# juggling_ballsch.net
KiCad netlist of a schematic drawn in EAGLE
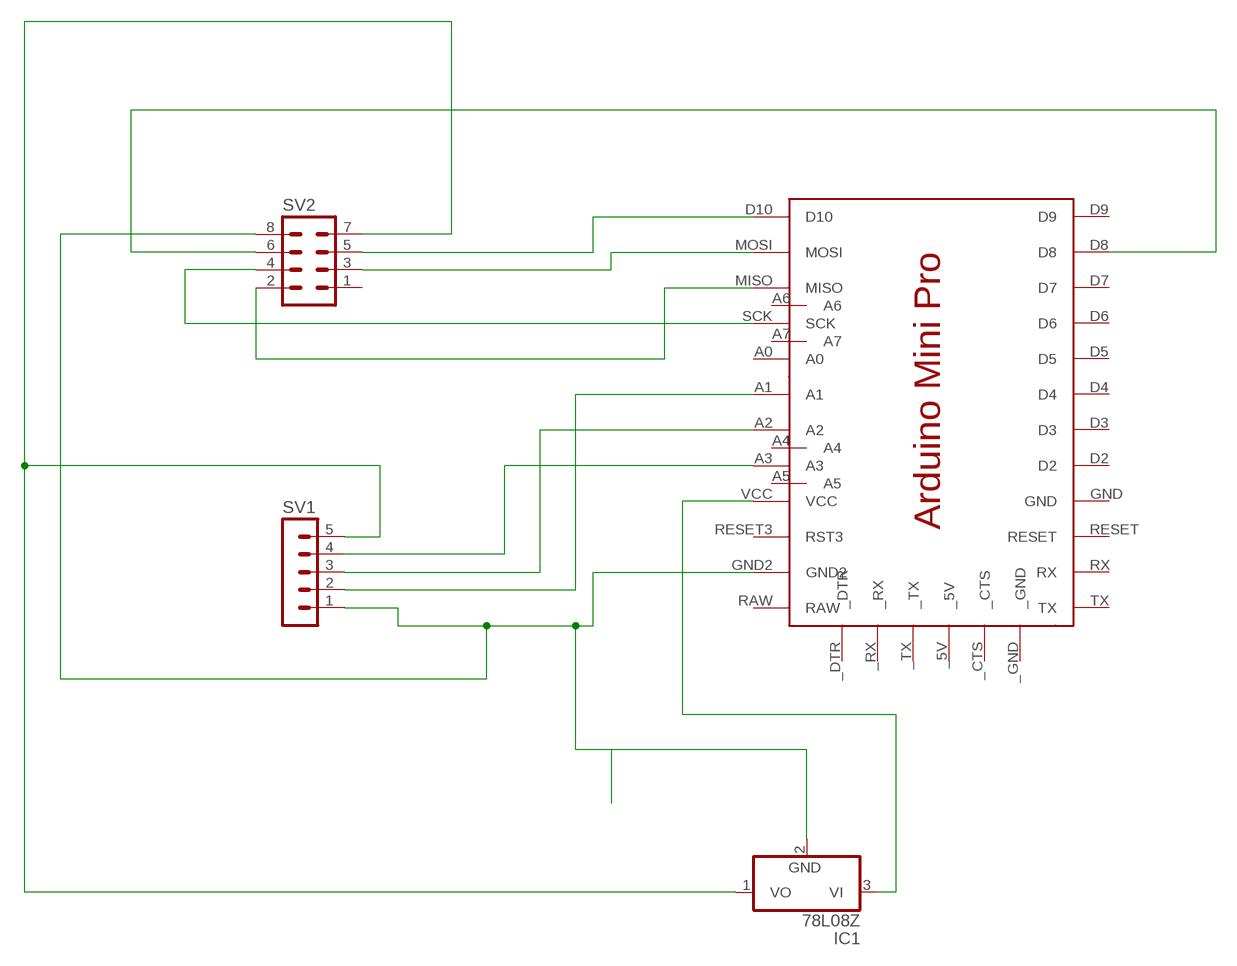
[diagram p0: schematic, sheet 1]

(export (version "E")
  (design (tool "Eeschema 10.0.6"))
  (components
    (comp (ref "IC1")
      (value "78L08Z")
      (footprint "eagle-import:TO92")
      (libsource (lib "eagle-import") (part "78ZL08"))
    )
    (comp (ref "SV1")
      (value "MA05-1")
      (footprint "eagle-import:MA05-1")
      (libsource (lib "eagle-import") (part "MA05-1"))
    )
    (comp (ref "SV2")
      (value "MA04-2")
      (footprint "eagle-import:MA04-2")
      (libsource (lib "eagle-import") (part "MA04-2"))
    )
    (comp (ref "U$1")
      (value "ARDMINIPRO")
      (footprint "eagle-import:ARDMINIPRO")
      (libsource (lib "eagle-import") (part "ARDMINIPRO"))
    )
  )
  (nets
    (net (code "1") (name "Net-(IC1-GND)") (class "Default")
      (node (ref "IC1") (pin "2") (pinfunction "GND_2") (pintype "passive"))
      (node (ref "SV1") (pin "1") (pinfunction "1_1") (pintype "passive"))
      (node (ref "SV2") (pin "8") (pinfunction "8_8") (pintype "passive"))
      (node (ref "U$1") (pin "GND2") (pinfunction "GND2_GND2") (pintype "bidirectional"))
    )
    (net (code "2") (name "Net-(IC1-VI)") (class "Default")
      (node (ref "IC1") (pin "3") (pinfunction "VI_3") (pintype "input"))
      (node (ref "U$1") (pin "VCC") (pinfunction "VCC_VCC") (pintype "bidirectional"))
    )
    (net (code "3") (name "Net-(IC1-VO)") (class "Default")
      (node (ref "IC1") (pin "1") (pinfunction "VO_1") (pintype "passive"))
      (node (ref "SV1") (pin "5") (pinfunction "5_5") (pintype "passive"))
      (node (ref "SV2") (pin "7") (pinfunction "7_7") (pintype "passive"))
    )
    (net (code "4") (name "Net-(SV1-Pad2)") (class "Default")
      (node (ref "SV1") (pin "2") (pinfunction "2_2") (pintype "passive"))
      (node (ref "U$1") (pin "A1") (pinfunction "A1_A1") (pintype "bidirectional"))
    )
    (net (code "5") (name "Net-(SV1-Pad3)") (class "Default")
      (node (ref "SV1") (pin "3") (pinfunction "3_3") (pintype "passive"))
      (node (ref "U$1") (pin "A2") (pinfunction "A2_A2") (pintype "bidirectional"))
    )
    (net (code "6") (name "Net-(SV1-Pad4)") (class "Default")
      (node (ref "SV1") (pin "4") (pinfunction "4_4") (pintype "passive"))
      (node (ref "U$1") (pin "A3") (pinfunction "A3_A3") (pintype "bidirectional"))
    )
    (net (code "7") (name "Net-(SV2-Pad2)") (class "Default")
      (node (ref "SV2") (pin "2") (pinfunction "2_2") (pintype "passive"))
      (node (ref "U$1") (pin "MISO") (pinfunction "MISO_MISO") (pintype "bidirectional"))
    )
    (net (code "8") (name "Net-(SV2-Pad3)") (class "Default")
      (node (ref "SV2") (pin "3") (pinfunction "3_3") (pintype "passive"))
      (node (ref "U$1") (pin "MOSI") (pinfunction "MOSI_MOSI") (pintype "bidirectional"))
    )
    (net (code "9") (name "Net-(SV2-Pad4)") (class "Default")
      (node (ref "SV2") (pin "4") (pinfunction "4_4") (pintype "passive"))
      (node (ref "U$1") (pin "SCK") (pinfunction "SCK_SCK") (pintype "bidirectional"))
    )
    (net (code "10") (name "Net-(SV2-Pad5)") (class "Default")
      (node (ref "SV2") (pin "5") (pinfunction "5_5") (pintype "passive"))
      (node (ref "U$1") (pin "D10") (pinfunction "D10_D10") (pintype "bidirectional"))
    )
    (net (code "11") (name "Net-(SV2-Pad6)") (class "Default")
      (node (ref "SV2") (pin "6") (pinfunction "6_6") (pintype "passive"))
      (node (ref "U$1") (pin "D8") (pinfunction "D8_D8") (pintype "bidirectional"))
    )
    (net (code "12") (name "unconnected-(SV2-Pad1)") (class "Default")
      (node (ref "SV2") (pin "1") (pinfunction "1_1") (pintype "passive"))
    )
    (net (code "13") (name "unconnected-(U$1-PadA0)") (class "Default")
      (node (ref "U$1") (pin "A0") (pinfunction "A0_A0") (pintype "bidirectional"))
    )
    (net (code "14") (name "unconnected-(U$1-PadA4)") (class "Default")
      (node (ref "U$1") (pin "A4") (pinfunction "A4_A4") (pintype "bidirectional"))
    )
    (net (code "15") (name "unconnected-(U$1-PadA5)") (class "Default")
      (node (ref "U$1") (pin "A5") (pinfunction "A5_A5") (pintype "bidirectional"))
    )
    (net (code "16") (name "unconnected-(U$1-PadA6)") (class "Default")
      (node (ref "U$1") (pin "A6") (pinfunction "A6_A6") (pintype "bidirectional"))
    )
    (net (code "17") (name "unconnected-(U$1-PadA7)") (class "Default")
      (node (ref "U$1") (pin "A7") (pinfunction "A7_A7") (pintype "bidirectional"))
    )
    (net (code "18") (name "unconnected-(U$1-PadD2)") (class "Default")
      (node (ref "U$1") (pin "D2") (pinfunction "D2_D2") (pintype "bidirectional"))
    )
    (net (code "19") (name "unconnected-(U$1-PadD3)") (class "Default")
      (node (ref "U$1") (pin "D3") (pinfunction "D3_D3") (pintype "bidirectional"))
    )
    (net (code "20") (name "unconnected-(U$1-PadD4)") (class "Default")
      (node (ref "U$1") (pin "D4") (pinfunction "D4_D4") (pintype "bidirectional"))
    )
    (net (code "21") (name "unconnected-(U$1-PadD5)") (class "Default")
      (node (ref "U$1") (pin "D5") (pinfunction "D5_D5") (pintype "bidirectional"))
    )
    (net (code "22") (name "unconnected-(U$1-PadD6)") (class "Default")
      (node (ref "U$1") (pin "D6") (pinfunction "D6_D6") (pintype "bidirectional"))
    )
    (net (code "23") (name "unconnected-(U$1-PadD7)") (class "Default")
      (node (ref "U$1") (pin "D7") (pinfunction "D7_D7") (pintype "bidirectional"))
    )
    (net (code "24") (name "unconnected-(U$1-PadD9)") (class "Default")
      (node (ref "U$1") (pin "D9") (pinfunction "D9_D9") (pintype "bidirectional"))
    )
    (net (code "25") (name "unconnected-(U$1-PadGND)") (class "Default")
      (node (ref "U$1") (pin "GND") (pinfunction "GND_GND") (pintype "bidirectional"))
    )
    (net (code "26") (name "unconnected-(U$1-PadRAW)") (class "Default")
      (node (ref "U$1") (pin "RAW") (pinfunction "RAW_RAW") (pintype "bidirectional"))
    )
    (net (code "27") (name "unconnected-(U$1-PadRESET)") (class "Default")
      (node (ref "U$1") (pin "RESET") (pinfunction "RESET_RESET") (pintype "bidirectional"))
    )
    (net (code "28") (name "unconnected-(U$1-PadRX)") (class "Default")
      (node (ref "U$1") (pin "RX") (pinfunction "RX_RX") (pintype "bidirectional"))
    )
    (net (code "29") (name "unconnected-(U$1-PadTX)") (class "Default")
      (node (ref "U$1") (pin "TX") (pinfunction "TX_TX") (pintype "bidirectional"))
    )
    (net (code "30") (name "unconnected-(U$1-Pad_5V)") (class "Default")
      (node (ref "U$1") (pin "_5V") (pinfunction "_5V__5V") (pintype "bidirectional"))
    )
    (net (code "31") (name "unconnected-(U$1-Pad_CTS)") (class "Default")
      (node (ref "U$1") (pin "_CTS") (pinfunction "_CTS__CTS") (pintype "bidirectional"))
    )
    (net (code "32") (name "unconnected-(U$1-Pad_DTR)") (class "Default")
      (node (ref "U$1") (pin "_DTR") (pinfunction "_DTR__DTR") (pintype "bidirectional"))
    )
    (net (code "33") (name "unconnected-(U$1-Pad_GND)") (class "Default")
      (node (ref "U$1") (pin "_GND") (pinfunction "_GND__GND") (pintype "bidirectional"))
    )
    (net (code "34") (name "unconnected-(U$1-Pad_RX)") (class "Default")
      (node (ref "U$1") (pin "_RX") (pinfunction "_RX__RX") (pintype "bidirectional"))
    )
    (net (code "35") (name "unconnected-(U$1-Pad_TX)") (class "Default")
      (node (ref "U$1") (pin "_TX") (pinfunction "_TX__TX") (pintype "bidirectional"))
    )
    (net (code "36") (name "unconnected-(U$1-RST3-PadRESET3)") (class "Default")
      (node (ref "U$1") (pin "RESET3") (pinfunction "RST3_RESET3") (pintype "bidirectional"))
    )
  )
)
